# CANbus.net
KiCad netlist of a schematic drawn in Altium Designer
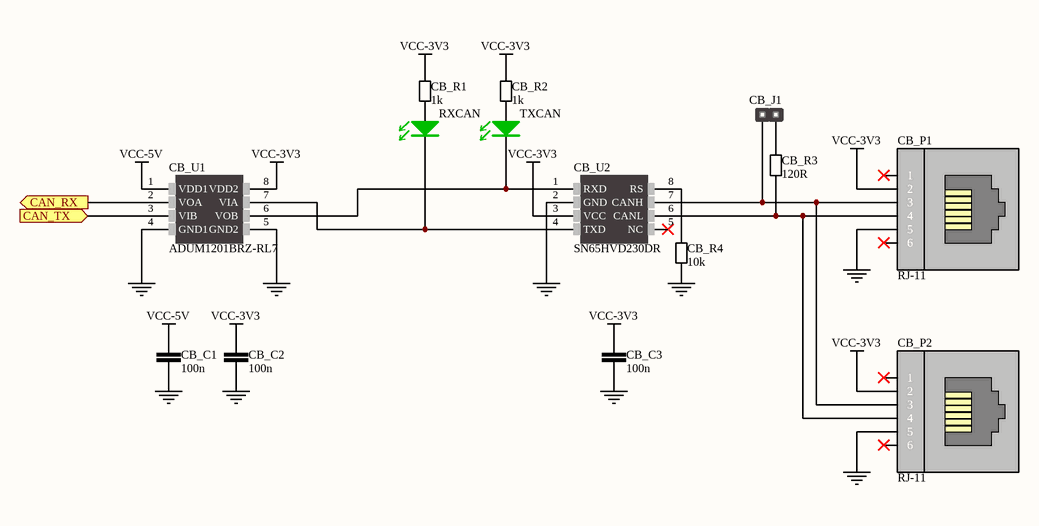
[diagram p0: CANbus.SchDoc]

(export (version "E")
  (design (tool "Eeschema 10.0.6"))
  (components
    (comp (ref "CB_C1")
      (value "100n")
      (footprint "CER_0603")
      (description "CAP CER 100n 10V X5R 10% 0603")
      (libsource (lib "Capacitors") (part "06032105"))
    )
    (comp (ref "CB_C2")
      (value "100n")
      (footprint "CER_0603")
      (description "CAP CER 100n 10V X5R 10% 0603")
      (libsource (lib "Capacitors") (part "06032105"))
    )
    (comp (ref "CB_C3")
      (value "100n")
      (footprint "CER_0603")
      (description "CAP CER 100n 10V X5R 10% 0603")
      (libsource (lib "Capacitors") (part "06032105"))
    )
    (comp (ref "CB_J1")
      (value "*")
      (footprint "HM1x2")
      (libsource (lib "Electro_Mechanical") (part "HEADER_1x2"))
    )
    (comp (ref "CB_P1")
      (value "RJ-11")
      (footprint "RJ11-6N-B")
      (libsource (lib "Electro_Mechanical") (part "00000001"))
    )
    (comp (ref "CB_P2")
      (value "RJ-11")
      (footprint "RJ11-6N-B")
      (libsource (lib "Electro_Mechanical") (part "00000001"))
    )
    (comp (ref "CB_R1")
      (value "1k")
      (footprint "RESC2013X38N-0805-NOOVERLAY")
      (description "RES SMD 1 kOhm 1/8W 0805")
      (fields (field (name "POWER") "0.125W, 1/8W"))
      (libsource (lib "Resistors") (part "00001001"))
    )
    (comp (ref "CB_R2")
      (value "1k")
      (footprint "RESC2013X38N-0805-NOOVERLAY")
      (description "RES SMD 1 kOhm 1/8W 0805")
      (fields (field (name "POWER") "0.125W, 1/8W"))
      (libsource (lib "Resistors") (part "00001001"))
    )
    (comp (ref "CB_R3")
      (value "120R")
      (footprint "RESC2013X38N-0805-NOOVERLAY")
      (description "RES SMD 120 Ohm 1/8W 0805")
      (libsource (lib "Resistors") (part "000001200"))
    )
    (comp (ref "CB_R4")
      (value "10k")
      (footprint "RESC2013X38N-0805-NOOVERLAY")
      (description "RES SMD 10 kOhm 1/8W 0805")
      (libsource (lib "Resistors") (part "000001002"))
    )
    (comp (ref "CB_U1")
      (value "ADUM1201BRZ-RL7")
      (footprint "SOIC-8")
      (description "DGTL ISO 2.5KV GEN PURP 8SOIC")
      (libsource (lib "Integrated_circuits") (part "ADUM1201BRZ"))
    )
    (comp (ref "CB_U2")
      (value "SN65HVD230DR")
      (footprint "SOIC-8")
      (description "IC EMC CAN TRANSCEIVER 8-SOIC")
      (libsource (lib "Integrated_circuits") (part "SN65HVD230"))
    )
    (comp (ref "RXCAN")
      (value "LED GREEN")
      (footprint "LED_GREEN_0805")
      (description "LED GREEN CLEAR 0805 SMD")
      (fields
        (field (name "MANUFACTURER") "Kingbright")
        (field (name "MANUFACTURER PART NUMBER") "APT2012SGC")
      )
      (libsource (lib "Discrete_Semiconductor") (part "LED_GREEN 0805"))
    )
    (comp (ref "TXCAN")
      (value "LED GREEN")
      (footprint "LED_GREEN_0805")
      (description "LED GREEN CLEAR 0805 SMD")
      (fields
        (field (name "MANUFACTURER") "Kingbright")
        (field (name "MANUFACTURER PART NUMBER") "APT2012SGC")
      )
      (libsource (lib "Discrete_Semiconductor") (part "LED_GREEN 0805"))
    )
  )
  (nets
    (net (code "1") (name "/CAN_RX") (class "Default")
      (node (ref "CB_U1") (pin "2") (pinfunction "VOA_2") (pintype "passive"))
    )
    (net (code "2") (name "/CAN_TX") (class "Default")
      (node (ref "CB_U1") (pin "3") (pinfunction "VIB_3") (pintype "passive"))
    )
    (net (code "3") (name "GND") (class "Default")
      (node (ref "CB_C1") (pin "1") (pinfunction "1_1") (pintype "passive"))
      (node (ref "CB_C2") (pin "1") (pinfunction "1_1") (pintype "passive"))
      (node (ref "CB_C3") (pin "1") (pinfunction "1_1") (pintype "passive"))
      (node (ref "CB_P1") (pin "5") (pinfunction "5_5") (pintype "passive"))
      (node (ref "CB_P2") (pin "5") (pinfunction "5_5") (pintype "passive"))
      (node (ref "CB_R4") (pin "1") (pinfunction "1_1") (pintype "passive"))
      (node (ref "CB_U1") (pin "4") (pinfunction "GND1_4") (pintype "passive"))
      (node (ref "CB_U1") (pin "5") (pinfunction "GND2_5") (pintype "passive"))
      (node (ref "CB_U2") (pin "2") (pinfunction "GND_2") (pintype "passive"))
    )
    (net (code "4") (name "Net-(CB_J1-1-Pad2)") (class "Default")
      (node (ref "CB_J1") (pin "2") (pinfunction "1_2") (pintype "passive"))
      (node (ref "CB_R3") (pin "2") (pinfunction "2_2") (pintype "passive"))
    )
    (net (code "5") (name "Net-(CB_U1-VIA)") (class "Default")
      (node (ref "CB_U1") (pin "7") (pinfunction "VIA_7") (pintype "passive"))
      (node (ref "CB_U2") (pin "4") (pinfunction "TXD_4") (pintype "passive"))
      (node (ref "RXCAN") (pin "1") (pinfunction "C_1") (pintype "passive"))
    )
    (net (code "6") (name "Net-(CB_U1-VOB)") (class "Default")
      (node (ref "CB_U1") (pin "6") (pinfunction "VOB_6") (pintype "passive"))
      (node (ref "CB_U2") (pin "1") (pinfunction "RXD_1") (pintype "passive"))
      (node (ref "TXCAN") (pin "1") (pinfunction "C_1") (pintype "passive"))
    )
    (net (code "7") (name "Net-(CB_U2-CANH)") (class "Default")
      (node (ref "CB_J1") (pin "1") (pinfunction "1_1") (pintype "passive"))
      (node (ref "CB_P1") (pin "3") (pinfunction "3_3") (pintype "passive"))
      (node (ref "CB_P2") (pin "3") (pinfunction "3_3") (pintype "passive"))
      (node (ref "CB_U2") (pin "7") (pinfunction "CANH_7") (pintype "passive"))
    )
    (net (code "8") (name "Net-(CB_U2-CANL)") (class "Default")
      (node (ref "CB_P1") (pin "4") (pinfunction "4_4") (pintype "passive"))
      (node (ref "CB_P2") (pin "4") (pinfunction "4_4") (pintype "passive"))
      (node (ref "CB_R3") (pin "1") (pinfunction "1_1") (pintype "passive"))
      (node (ref "CB_U2") (pin "6") (pinfunction "CANL_6") (pintype "passive"))
    )
    (net (code "9") (name "Net-(CB_U2-RS)") (class "Default")
      (node (ref "CB_R4") (pin "2") (pinfunction "2_2") (pintype "passive"))
      (node (ref "CB_U2") (pin "8") (pinfunction "RS_8") (pintype "passive"))
    )
    (net (code "10") (name "Net-(RXCAN-A)") (class "Default")
      (node (ref "CB_R1") (pin "1") (pinfunction "1_1") (pintype "passive"))
      (node (ref "RXCAN") (pin "2") (pinfunction "A_2") (pintype "passive"))
    )
    (net (code "11") (name "Net-(TXCAN-A)") (class "Default")
      (node (ref "CB_R2") (pin "1") (pinfunction "1_1") (pintype "passive"))
      (node (ref "TXCAN") (pin "2") (pinfunction "A_2") (pintype "passive"))
    )
    (net (code "12") (name "VCC-3V3") (class "Default")
      (node (ref "CB_C2") (pin "2") (pinfunction "2_2") (pintype "passive"))
      (node (ref "CB_C3") (pin "2") (pinfunction "2_2") (pintype "passive"))
      (node (ref "CB_P1") (pin "2") (pinfunction "2_2") (pintype "passive"))
      (node (ref "CB_P2") (pin "2") (pinfunction "2_2") (pintype "passive"))
      (node (ref "CB_R1") (pin "2") (pinfunction "2_2") (pintype "passive"))
      (node (ref "CB_R2") (pin "2") (pinfunction "2_2") (pintype "passive"))
      (node (ref "CB_U1") (pin "8") (pinfunction "VDD2_8") (pintype "passive"))
      (node (ref "CB_U2") (pin "3") (pinfunction "VCC_3") (pintype "passive"))
    )
    (net (code "13") (name "VCC-5V") (class "Default")
      (node (ref "CB_C1") (pin "2") (pinfunction "2_2") (pintype "passive"))
      (node (ref "CB_U1") (pin "1") (pinfunction "VDD1_1") (pintype "passive"))
    )
    (net (code "14") (name "unconnected-(CB_P1-Pad1)") (class "Default")
      (node (ref "CB_P1") (pin "1") (pinfunction "1_1") (pintype "passive+no_connect"))
    )
    (net (code "15") (name "unconnected-(CB_P1-Pad6)") (class "Default")
      (node (ref "CB_P1") (pin "6") (pinfunction "6_6") (pintype "passive+no_connect"))
    )
    (net (code "16") (name "unconnected-(CB_P2-Pad1)") (class "Default")
      (node (ref "CB_P2") (pin "1") (pinfunction "1_1") (pintype "passive+no_connect"))
    )
    (net (code "17") (name "unconnected-(CB_P2-Pad6)") (class "Default")
      (node (ref "CB_P2") (pin "6") (pinfunction "6_6") (pintype "passive+no_connect"))
    )
    (net (code "18") (name "unconnected-(CB_U2-NC-Pad5)") (class "Default")
      (node (ref "CB_U2") (pin "5") (pinfunction "NC_5") (pintype "passive+no_connect"))
    )
  )
)
